# SSFocuser-B-TMC2208-KCTW.net
KiCad netlist of a schematic drawn in Altium Designer
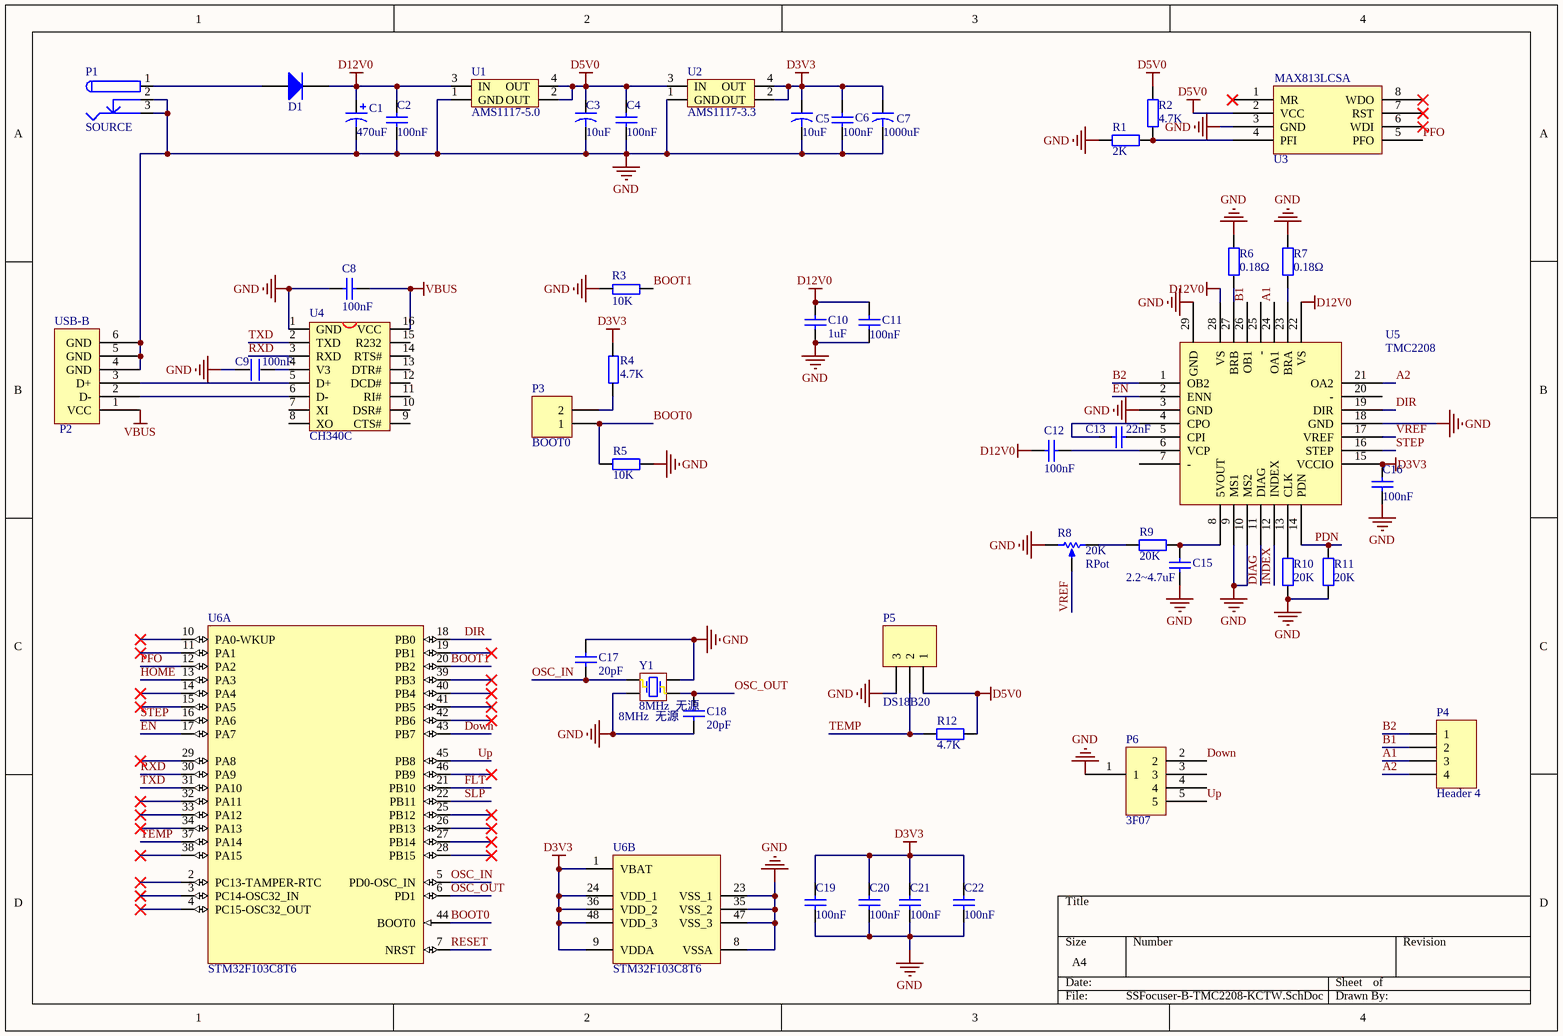
[diagram p0: SSFocuser-B-TMC2208-KCTW.SchDoc]

(export (version "E")
  (design (tool "Eeschema 10.0.6"))
  (components
    (comp (ref "C1")
      (value "470uF")
      (footprint "16V/470U(CD10X10D5)")
      (description "470UF      16V      CD10X10D5")
      (libsource (lib "平台原理图symbol图库V1.0") (part "C470UF016S"))
    )
    (comp (ref "C2")
      (value "100nF")
      (footprint "0603C")
      (description "Capacitor")
      (fields (field (name "PUBLISHER") "Altium Limited"))
      (libsource (lib "Crazy_PCB") (part "Cap"))
    )
    (comp (ref "C3")
      (value "10uF")
      (footprint "3216")
      (fields (field (name "VAULE") "10uF"))
      (libsource (lib "Crazy_PCB") (part "CAP2"))
    )
    (comp (ref "C4")
      (value "100nF")
      (footprint "0603C")
      (description "Capacitor")
      (fields (field (name "PUBLISHER") "Altium Limited"))
      (libsource (lib "Crazy_PCB") (part "Cap"))
    )
    (comp (ref "C5")
      (value "10uF")
      (footprint "3216")
      (fields (field (name "VAULE") "10uF"))
      (libsource (lib "Crazy_PCB") (part "CAP2"))
    )
    (comp (ref "C6")
      (value "100nF")
      (footprint "0603C")
      (description "Capacitor")
      (fields (field (name "PUBLISHER") "Altium Limited"))
      (libsource (lib "Crazy_PCB") (part "Cap"))
    )
    (comp (ref "C7")
      (value "1000uF")
      (footprint "16V/470U(CD10X10D5)")
      (fields (field (name "VAULE") "1000uF"))
      (libsource (lib "Crazy_PCB") (part "CAP2"))
    )
    (comp (ref "C8")
      (value "100nF")
      (footprint "0603C")
      (description "Capacitor")
      (fields (field (name "PUBLISHER") "Altium Limited"))
      (libsource (lib "Crazy_PCB") (part "Cap"))
    )
    (comp (ref "C9")
      (value "100nF")
      (footprint "0603C")
      (libsource (lib "WarShip V3 STM32103封装库") (part "C"))
    )
    (comp (ref "C10")
      (value "1uF")
      (footprint "1206C")
      (description "Capacitor")
      (fields (field (name "PUBLISHER") "Altium Limited"))
      (libsource (lib "Crazy_PCB") (part "Cap"))
    )
    (comp (ref "C11")
      (value "100nF")
      (footprint "0603C")
      (description "Capacitor")
      (fields (field (name "PUBLISHER") "Altium Limited"))
      (libsource (lib "Crazy_PCB") (part "Cap"))
    )
    (comp (ref "C12")
      (value "100nF")
      (footprint "0603C")
      (description "Capacitor")
      (fields (field (name "PUBLISHER") "Altium Limited"))
      (libsource (lib "Crazy_PCB") (part "Cap"))
    )
    (comp (ref "C13")
      (value "22nF")
      (footprint "0603C")
      (description "Capacitor")
      (fields (field (name "PUBLISHER") "Altium Limited"))
      (libsource (lib "Crazy_PCB") (part "Cap"))
    )
    (comp (ref "C15")
      (value "2.2~4.7uF")
      (footprint "0603C")
      (description "Capacitor")
      (fields (field (name "PUBLISHER") "Altium Limited"))
      (libsource (lib "Crazy_PCB") (part "Cap"))
    )
    (comp (ref "C16")
      (value "100nF")
      (footprint "0603C")
      (description "Capacitor")
      (fields (field (name "PUBLISHER") "Altium Limited"))
      (libsource (lib "Crazy_PCB") (part "Cap"))
    )
    (comp (ref "C17")
      (value "20pF")
      (footprint "0603C")
      (description "Capacitor")
      (fields (field (name "PUBLISHER") "Altium Limited"))
      (libsource (lib "JL_SCH") (part "Cap"))
    )
    (comp (ref "C18")
      (value "20pF")
      (footprint "0603C")
      (description "Capacitor")
      (fields (field (name "PUBLISHER") "Altium Limited"))
      (libsource (lib "JL_SCH") (part "Cap"))
    )
    (comp (ref "C19")
      (value "100nF")
      (footprint "0603C")
      (description "Capacitor")
      (fields (field (name "PUBLISHER") "Altium Limited"))
      (libsource (lib "Crazy_PCB") (part "Cap"))
    )
    (comp (ref "C20")
      (value "100nF")
      (footprint "0603C")
      (description "Capacitor")
      (fields (field (name "PUBLISHER") "Altium Limited"))
      (libsource (lib "Crazy_PCB") (part "Cap"))
    )
    (comp (ref "C21")
      (value "100nF")
      (footprint "0603C")
      (description "Capacitor")
      (fields (field (name "PUBLISHER") "Altium Limited"))
      (libsource (lib "Crazy_PCB") (part "Cap"))
    )
    (comp (ref "C22")
      (value "100nF")
      (footprint "0603C")
      (description "Capacitor")
      (fields (field (name "PUBLISHER") "Altium Limited"))
      (libsource (lib "Crazy_PCB") (part "Cap"))
    )
    (comp (ref "D1")
      (value "M7")
      (footprint "DO-214AC")
      (description "High Conductance Fast Diode")
      (fields (field (name "PUBLISHER") "Altium Limited"))
      (libsource (lib "Crazy_PCB") (part "Diode"))
    )
    (comp (ref "P1")
      (value "SOURCE")
      (footprint "DC005")
      (fields (field (name "PUBLISHER") "Altium Limited"))
      (libsource (lib "Crazy_PCB") (part "SOURCE"))
    )
    (comp (ref "P2") (value "USB-B") (footprint "USB-B") (libsource (lib "DX") (part "USB-B")))
    (comp (ref "P3")
      (value "BOOT0")
      (footprint "HDR1X2")
      (description "Header, 2-Pin")
      (fields (field (name "PUBLISHER") "Altium Limited"))
      (libsource (lib "Miscellaneous Connectors") (part "MHDR1X2"))
    )
    (comp (ref "P4")
      (value "Header 4")
      (footprint "XH_4_V")
      (description "Header, 4-Pin")
      (fields (field (name "PUBLISHER") "Altium Limited"))
      (libsource (lib "Miscellaneous Connectors") (part "Header 4"))
    )
    (comp (ref "P5")
      (value "DS18B20")
      (footprint "TO-92B")
      (description "Header, 3-Pin")
      (fields (field (name "PUBLISHER") "Altium Limited"))
      (libsource (lib "Miscellaneous Connectors") (part "Header 3"))
    )
    (comp (ref "P6")
      (value "3F07")
      (footprint "3F07")
      (description "EarPhone3.5")
      (libsource (lib "SS") (part "3F07"))
    )
    (comp (ref "R1")
      (value "2K")
      (footprint "0603R")
      (description "Resistor")
      (fields (field (name "PUBLISHER") "Altium Limited"))
      (libsource (lib "") (part "RES_3"))
    )
    (comp (ref "R2")
      (value "4.7K")
      (footprint "0603R")
      (description "Resistor")
      (fields (field (name "PUBLISHER") "Altium Limited"))
      (libsource (lib "Crazy_PCB") (part "RES"))
    )
    (comp (ref "R3") (value "10K") (footprint "0603R") (libsource (lib "WarShip V3 STM32103封装库") (part "R")))
    (comp (ref "R4") (value "4.7K") (footprint "0603R") (libsource (lib "WarShip V3 STM32103封装库") (part "R")))
    (comp (ref "R5")
      (value "10K")
      (footprint "0603R")
      (description "Resistor")
      (fields (field (name "PUBLISHER") "Altium Limited"))
      (libsource (lib "") (part "RES_2"))
    )
    (comp (ref "R6")
      (value "0.18Ω")
      (footprint "1206R")
      (description "Resistor")
      (fields (field (name "PUBLISHER") "Altium Limited"))
      (libsource (lib "") (part "RES_1"))
    )
    (comp (ref "R7")
      (value "0.18Ω")
      (footprint "1206R")
      (description "Resistor")
      (fields (field (name "PUBLISHER") "Altium Limited"))
      (libsource (lib "") (part "RES_1"))
    )
    (comp (ref "R8")
      (value "RPot")
      (footprint "VR_SMD")
      (description "Potentiometer")
      (fields (field (name "ALTIUM_VALUE") "20K") (field (name "PUBLISHER") "Altium Limited"))
      (libsource (lib "Miscellaneous Devices") (part "RPot"))
    )
    (comp (ref "R9")
      (value "20K")
      (footprint "0603R")
      (description "Resistor")
      (fields (field (name "PUBLISHER") "Altium Limited"))
      (libsource (lib "") (part "RES_3"))
    )
    (comp (ref "R10")
      (value "20K")
      (footprint "0603R")
      (description "Resistor")
      (fields (field (name "PUBLISHER") "Altium Limited"))
      (libsource (lib "Crazy_PCB") (part "RES"))
    )
    (comp (ref "R11")
      (value "20K")
      (footprint "0603R")
      (description "Resistor")
      (fields (field (name "PUBLISHER") "Altium Limited"))
      (libsource (lib "Crazy_PCB") (part "RES"))
    )
    (comp (ref "R12")
      (value "4.7K")
      (footprint "0603R")
      (description "Resistor")
      (fields (field (name "PUBLISHER") "Altium Limited"))
      (libsource (lib "") (part "RES_2"))
    )
    (comp (ref "U1")
      (value "AMS1117-5.0")
      (footprint "SOT223")
      (libsource (lib "MiniSTM32 V3.0封装库") (part "AMS1117"))
    )
    (comp (ref "U2")
      (value "AMS1117-3.3")
      (footprint "SOT223")
      (libsource (lib "MiniSTM32 V3.0封装库") (part "AMS1117"))
    )
    (comp (ref "U3") (value "MAX813LCSA") (footprint "SOP-8") (libsource (lib "DX") (part "MAX813L")))
    (comp (ref "U4")
      (value "CH340C")
      (footprint "SO-16")
      (description "USB2UART")
      (libsource (lib "WarShip V3 STM32103封装库") (part "CH340G"))
    )
    (comp (ref "U5") (value "TMC2208") (footprint "QFN28") (libsource (lib "SS") (part "TMC2208")))
    (comp (ref "U6")
      (value "STM32F103C8T6")
      (footprint "LQFP48_N")
      (libsource (lib "STMicroelectronics STM32 F1") (part "STM32F103C8T6"))
    )
    (comp (ref "Y1")
      (value "8MHz  无源")
      (footprint "X3225")
      (description "Crystal Oscillator")
      (fields (field (name "ALTIUM_VALUE") "8MHz  无源") (field (name "PUBLISHER") "Altium Limited"))
      (libsource (lib "JL_SCH") (part "XTAL_1"))
    )
  )
  (nets
    (net (code "1") (name "/A1") (class "Default")
      (node (ref "P4") (pin "3") (pinfunction "3_3") (pintype "passive"))
      (node (ref "U5") (pin "24") (pinfunction "OA1_24") (pintype "passive"))
    )
    (net (code "2") (name "/A2") (class "Default")
      (node (ref "P4") (pin "4") (pinfunction "4_4") (pintype "passive"))
      (node (ref "U5") (pin "21") (pinfunction "OA2_21") (pintype "passive"))
    )
    (net (code "3") (name "/B1") (class "Default")
      (node (ref "P4") (pin "2") (pinfunction "2_2") (pintype "passive"))
      (node (ref "U5") (pin "26") (pinfunction "OB1_26") (pintype "passive"))
    )
    (net (code "4") (name "/B2") (class "Default")
      (node (ref "P4") (pin "1") (pinfunction "1_1") (pintype "passive"))
      (node (ref "U5") (pin "1") (pinfunction "OB2_1") (pintype "passive"))
    )
    (net (code "5") (name "/BOOT0") (class "Default")
      (node (ref "P3") (pin "1") (pinfunction "1_1") (pintype "passive"))
      (node (ref "R5") (pin "1") (pinfunction "1_1") (pintype "passive"))
      (node (ref "U6") (pin "44") (pinfunction "BOOT0_44") (pintype "input"))
    )
    (net (code "6") (name "/BOOT1") (class "Default")
      (node (ref "R3") (pin "2") (pintype "passive"))
      (node (ref "U6") (pin "20") (pinfunction "PB2_20") (pintype "bidirectional"))
    )
    (net (code "7") (name "/DIAG") (class "Default")
      (node (ref "U5") (pin "11") (pinfunction "DIAG_11") (pintype "passive"))
    )
    (net (code "8") (name "/DIR") (class "Default")
      (node (ref "U5") (pin "19") (pinfunction "DIR_19") (pintype "passive"))
      (node (ref "U6") (pin "18") (pinfunction "PB0_18") (pintype "bidirectional"))
    )
    (net (code "9") (name "/Down") (class "Default")
      (node (ref "P6") (pin "2") (pinfunction "2_2") (pintype "passive"))
      (node (ref "U6") (pin "43") (pinfunction "PB7_43") (pintype "bidirectional"))
    )
    (net (code "10") (name "/EN") (class "Default")
      (node (ref "U5") (pin "2") (pinfunction "ENN_2") (pintype "passive"))
      (node (ref "U6") (pin "17") (pinfunction "PA7_17") (pintype "bidirectional"))
    )
    (net (code "11") (name "/FLT") (class "Default")
      (node (ref "U6") (pin "21") (pinfunction "PB10_21") (pintype "bidirectional"))
    )
    (net (code "12") (name "/HOME") (class "Default")
      (node (ref "U6") (pin "13") (pinfunction "PA3_13") (pintype "bidirectional"))
    )
    (net (code "13") (name "/INDEX") (class "Default")
      (node (ref "U5") (pin "12") (pinfunction "INDEX_12") (pintype "passive"))
    )
    (net (code "14") (name "/OSC_IN") (class "Default")
      (node (ref "C17") (pin "1") (pinfunction "1_1") (pintype "passive"))
      (node (ref "U6") (pin "5") (pinfunction "PD0-OSC_IN_5") (pintype "bidirectional"))
      (node (ref "Y1") (pin "1") (pinfunction "OSC1_1") (pintype "passive"))
    )
    (net (code "15") (name "/OSC_OUT") (class "Default")
      (node (ref "C18") (pin "1") (pinfunction "1_1") (pintype "passive"))
      (node (ref "U6") (pin "6") (pinfunction "PD1_6") (pintype "bidirectional"))
      (node (ref "Y1") (pin "3") (pinfunction "OSC2_3") (pintype "passive"))
    )
    (net (code "16") (name "/PDN") (class "Default")
      (node (ref "R11") (pin "2") (pinfunction "2_2") (pintype "passive"))
      (node (ref "U5") (pin "14") (pinfunction "PDN_14") (pintype "passive"))
    )
    (net (code "17") (name "/PFO") (class "Default")
      (node (ref "U3") (pin "5") (pinfunction "PFO_5") (pintype "passive"))
      (node (ref "U6") (pin "12") (pinfunction "PA2_12") (pintype "bidirectional"))
    )
    (net (code "18") (name "/RESET") (class "Default")
      (node (ref "U6") (pin "7") (pinfunction "NRST_7") (pintype "bidirectional"))
    )
    (net (code "19") (name "/RXD") (class "Default")
      (node (ref "U4") (pin "3") (pinfunction "RXD_3") (pintype "passive"))
      (node (ref "U6") (pin "30") (pinfunction "PA9_30") (pintype "bidirectional"))
    )
    (net (code "20") (name "/SLP") (class "Default")
      (node (ref "U6") (pin "22") (pinfunction "PB11_22") (pintype "bidirectional"))
    )
    (net (code "21") (name "/STEP") (class "Default")
      (node (ref "U5") (pin "16") (pinfunction "STEP_16") (pintype "passive"))
      (node (ref "U6") (pin "16") (pinfunction "PA6_16") (pintype "bidirectional"))
    )
    (net (code "22") (name "/TEMP") (class "Default")
      (node (ref "P5") (pin "2") (pinfunction "2_2") (pintype "passive"))
      (node (ref "R12") (pin "1") (pinfunction "1_1") (pintype "passive"))
      (node (ref "U6") (pin "37") (pinfunction "PA14_37") (pintype "bidirectional"))
    )
    (net (code "23") (name "/TXD") (class "Default")
      (node (ref "U4") (pin "2") (pinfunction "TXD_2") (pintype "passive"))
      (node (ref "U6") (pin "31") (pinfunction "PA10_31") (pintype "bidirectional"))
    )
    (net (code "24") (name "/Up") (class "Default")
      (node (ref "P6") (pin "5") (pinfunction "5_5") (pintype "passive"))
      (node (ref "U6") (pin "45") (pinfunction "PB8_45") (pintype "bidirectional"))
    )
    (net (code "25") (name "/VREF") (class "Default")
      (node (ref "R8") (pin "3") (pinfunction "TAP_3") (pintype "passive"))
      (node (ref "U5") (pin "17") (pinfunction "VREF_17") (pintype "passive"))
    )
    (net (code "26") (name "D3V3") (class "Default")
      (node (ref "C16") (pin "2") (pinfunction "2_2") (pintype "passive"))
      (node (ref "C19") (pin "2") (pinfunction "2_2") (pintype "passive"))
      (node (ref "C20") (pin "2") (pinfunction "2_2") (pintype "passive"))
      (node (ref "C21") (pin "2") (pinfunction "2_2") (pintype "passive"))
      (node (ref "C22") (pin "2") (pinfunction "2_2") (pintype "passive"))
      (node (ref "C5") (pin "1") (pinfunction "1_1") (pintype "passive"))
      (node (ref "C6") (pin "2") (pinfunction "2_2") (pintype "passive"))
      (node (ref "C7") (pin "1") (pinfunction "1_1") (pintype "passive"))
      (node (ref "R4") (pin "2") (pintype "passive"))
      (node (ref "U2") (pin "2") (pinfunction "OUT_2") (pintype "passive"))
      (node (ref "U2") (pin "4") (pinfunction "OUT_4") (pintype "passive"))
      (node (ref "U5") (pin "15") (pinfunction "VCCIO_15") (pintype "passive"))
      (node (ref "U6") (pin "1") (pinfunction "VBAT_1") (pintype "power_in"))
      (node (ref "U6") (pin "24") (pinfunction "VDD_1_24") (pintype "power_in"))
      (node (ref "U6") (pin "36") (pinfunction "VDD_2_36") (pintype "power_in"))
      (node (ref "U6") (pin "48") (pinfunction "VDD_3_48") (pintype "power_in"))
      (node (ref "U6") (pin "9") (pinfunction "VDDA_9") (pintype "power_in"))
    )
    (net (code "27") (name "D5V0") (class "Default")
      (node (ref "C3") (pin "1") (pinfunction "1_1") (pintype "passive"))
      (node (ref "C4") (pin "2") (pinfunction "2_2") (pintype "passive"))
      (node (ref "P5") (pin "1") (pinfunction "1_1") (pintype "passive"))
      (node (ref "R12") (pin "2") (pinfunction "2_2") (pintype "passive"))
      (node (ref "R2") (pin "2") (pinfunction "2_2") (pintype "passive"))
      (node (ref "U1") (pin "2") (pinfunction "OUT_2") (pintype "passive"))
      (node (ref "U1") (pin "4") (pinfunction "OUT_4") (pintype "passive"))
      (node (ref "U2") (pin "3") (pinfunction "IN_3") (pintype "passive"))
      (node (ref "U3") (pin "2") (pinfunction "VCC_2") (pintype "passive"))
    )
    (net (code "28") (name "D12V0") (class "Default")
      (node (ref "C1") (pin "1") (pinfunction "1_1") (pintype "passive"))
      (node (ref "C10") (pin "1") (pinfunction "1_1") (pintype "passive"))
      (node (ref "C11") (pin "2") (pinfunction "2_2") (pintype "passive"))
      (node (ref "C12") (pin "2") (pinfunction "2_2") (pintype "passive"))
      (node (ref "C2") (pin "2") (pinfunction "2_2") (pintype "passive"))
      (node (ref "D1") (pin "2") (pinfunction "K_2") (pintype "passive"))
      (node (ref "U1") (pin "3") (pinfunction "IN_3") (pintype "passive"))
      (node (ref "U5") (pin "22") (pinfunction "VS_22") (pintype "passive"))
      (node (ref "U5") (pin "28") (pinfunction "VS_28") (pintype "passive"))
    )
    (net (code "29") (name "GND") (class "Default")
      (node (ref "C1") (pin "2") (pinfunction "2_2") (pintype "passive"))
      (node (ref "C10") (pin "2") (pinfunction "2_2") (pintype "passive"))
      (node (ref "C11") (pin "1") (pinfunction "1_1") (pintype "passive"))
      (node (ref "C15") (pin "1") (pinfunction "1_1") (pintype "passive"))
      (node (ref "C16") (pin "1") (pinfunction "1_1") (pintype "passive"))
      (node (ref "C17") (pin "2") (pinfunction "2_2") (pintype "passive"))
      (node (ref "C18") (pin "2") (pinfunction "2_2") (pintype "passive"))
      (node (ref "C19") (pin "1") (pinfunction "1_1") (pintype "passive"))
      (node (ref "C2") (pin "1") (pinfunction "1_1") (pintype "passive"))
      (node (ref "C20") (pin "1") (pinfunction "1_1") (pintype "passive"))
      (node (ref "C21") (pin "1") (pinfunction "1_1") (pintype "passive"))
      (node (ref "C22") (pin "1") (pinfunction "1_1") (pintype "passive"))
      (node (ref "C3") (pin "2") (pinfunction "2_2") (pintype "passive"))
      (node (ref "C4") (pin "1") (pinfunction "1_1") (pintype "passive"))
      (node (ref "C5") (pin "2") (pinfunction "2_2") (pintype "passive"))
      (node (ref "C6") (pin "1") (pinfunction "1_1") (pintype "passive"))
      (node (ref "C7") (pin "2") (pinfunction "2_2") (pintype "passive"))
      (node (ref "C8") (pin "1") (pinfunction "1_1") (pintype "passive"))
      (node (ref "C9") (pin "1") (pintype "passive"))
      (node (ref "P1") (pin "2") (pinfunction "2_2") (pintype "power_in"))
      (node (ref "P1") (pin "3") (pinfunction "3_3") (pintype "power_in"))
      (node (ref "P2") (pin "4") (pinfunction "GND_4") (pintype "passive"))
      (node (ref "P2") (pin "5") (pinfunction "GND_5") (pintype "passive"))
      (node (ref "P2") (pin "6") (pinfunction "GND_6") (pintype "passive"))
      (node (ref "P5") (pin "3") (pinfunction "3_3") (pintype "passive"))
      (node (ref "P6") (pin "1") (pinfunction "1_1") (pintype "passive"))
      (node (ref "R1") (pin "2") (pinfunction "2_2") (pintype "passive"))
      (node (ref "R10") (pin "1") (pinfunction "1_1") (pintype "passive"))
      (node (ref "R11") (pin "1") (pinfunction "1_1") (pintype "passive"))
      (node (ref "R3") (pin "1") (pintype "passive"))
      (node (ref "R5") (pin "2") (pinfunction "2_2") (pintype "passive"))
      (node (ref "R6") (pin "1") (pinfunction "1_1") (pintype "passive"))
      (node (ref "R7") (pin "1") (pinfunction "1_1") (pintype "passive"))
      (node (ref "R8") (pin "1") (pinfunction "TOP_1") (pintype "passive"))
      (node (ref "U1") (pin "1") (pinfunction "GND_1") (pintype "passive"))
      (node (ref "U2") (pin "1") (pinfunction "GND_1") (pintype "passive"))
      (node (ref "U3") (pin "3") (pinfunction "GND_3") (pintype "passive"))
      (node (ref "U4") (pin "1") (pinfunction "GND_1") (pintype "passive"))
      (node (ref "U5") (pin "10") (pinfunction "MS2_10") (pintype "passive"))
      (node (ref "U5") (pin "18") (pinfunction "GND_18") (pintype "passive"))
      (node (ref "U5") (pin "29") (pinfunction "GND_29") (pintype "passive"))
      (node (ref "U5") (pin "3") (pinfunction "GND_3") (pintype "passive"))
      (node (ref "U5") (pin "9") (pinfunction "MS1_9") (pintype "passive"))
      (node (ref "U6") (pin "23") (pinfunction "VSS_1_23") (pintype "power_in"))
      (node (ref "U6") (pin "35") (pinfunction "VSS_2_35") (pintype "power_in"))
      (node (ref "U6") (pin "47") (pinfunction "VSS_3_47") (pintype "power_in"))
      (node (ref "U6") (pin "8") (pinfunction "VSSA_8") (pintype "power_in"))
      (node (ref "Y1") (pin "2") (pinfunction "NA_2") (pintype "passive"))
      (node (ref "Y1") (pin "4") (pinfunction "NA_4") (pintype "passive"))
    )
    (net (code "30") (name "Net-(D1-A)") (class "Default")
      (node (ref "D1") (pin "1") (pinfunction "A_1") (pintype "passive"))
      (node (ref "P1") (pin "1") (pinfunction "1_1") (pintype "power_in"))
    )
    (net (code "31") (name "Net-(P2-D+)") (class "Default")
      (node (ref "P2") (pin "3") (pinfunction "D+_3") (pintype "passive"))
      (node (ref "U4") (pin "5") (pinfunction "D+_5") (pintype "passive"))
    )
    (net (code "32") (name "Net-(P2-D-)") (class "Default")
      (node (ref "P2") (pin "2") (pinfunction "D-_2") (pintype "passive"))
      (node (ref "U4") (pin "6") (pinfunction "D-_6") (pintype "passive"))
    )
    (net (code "33") (name "Net-(P3-Pad2)") (class "Default")
      (node (ref "P3") (pin "2") (pinfunction "2_2") (pintype "passive"))
      (node (ref "R4") (pin "1") (pintype "passive"))
    )
    (net (code "34") (name "Net-(R8-BOT)") (class "Default")
      (node (ref "R8") (pin "2") (pinfunction "BOT_2") (pintype "passive"))
      (node (ref "R9") (pin "2") (pinfunction "2_2") (pintype "passive"))
    )
    (net (code "35") (name "Net-(U3-PFI)") (class "Default")
      (node (ref "R1") (pin "1") (pinfunction "1_1") (pintype "passive"))
      (node (ref "R2") (pin "1") (pinfunction "1_1") (pintype "passive"))
      (node (ref "U3") (pin "4") (pinfunction "PFI_4") (pintype "passive"))
    )
    (net (code "36") (name "Net-(U4-V3)") (class "Default")
      (node (ref "C9") (pin "2") (pintype "passive"))
      (node (ref "U4") (pin "4") (pinfunction "V3_4") (pintype "passive"))
    )
    (net (code "37") (name "Net-(U5-5VOUT)") (class "Default")
      (node (ref "C15") (pin "2") (pinfunction "2_2") (pintype "passive"))
      (node (ref "R9") (pin "1") (pinfunction "1_1") (pintype "passive"))
      (node (ref "U5") (pin "8") (pinfunction "5VOUT_8") (pintype "passive"))
    )
    (net (code "38") (name "Net-(U5-BRA)") (class "Default")
      (node (ref "R7") (pin "2") (pinfunction "2_2") (pintype "passive"))
      (node (ref "U5") (pin "23") (pinfunction "BRA_23") (pintype "passive"))
    )
    (net (code "39") (name "Net-(U5-BRB)") (class "Default")
      (node (ref "R6") (pin "2") (pinfunction "2_2") (pintype "passive"))
      (node (ref "U5") (pin "27") (pinfunction "BRB_27") (pintype "passive"))
    )
    (net (code "40") (name "Net-(U5-CLK)") (class "Default")
      (node (ref "R10") (pin "2") (pinfunction "2_2") (pintype "passive"))
      (node (ref "U5") (pin "13") (pinfunction "CLK_13") (pintype "passive"))
    )
    (net (code "41") (name "Net-(U5-CPI)") (class "Default")
      (node (ref "C13") (pin "1") (pinfunction "1_1") (pintype "passive"))
      (node (ref "U5") (pin "5") (pinfunction "CPI_5") (pintype "passive"))
    )
    (net (code "42") (name "Net-(U5-CPO)") (class "Default")
      (node (ref "C13") (pin "2") (pinfunction "2_2") (pintype "passive"))
      (node (ref "U5") (pin "4") (pinfunction "CPO_4") (pintype "passive"))
    )
    (net (code "43") (name "Net-(U5-VCP)") (class "Default")
      (node (ref "C12") (pin "1") (pinfunction "1_1") (pintype "passive"))
      (node (ref "U5") (pin "6") (pinfunction "VCP_6") (pintype "passive"))
    )
    (net (code "44") (name "VBUS") (class "Default")
      (node (ref "C8") (pin "2") (pinfunction "2_2") (pintype "passive"))
      (node (ref "P2") (pin "1") (pinfunction "VCC_1") (pintype "passive"))
      (node (ref "U4") (pin "16") (pinfunction "VCC_16") (pintype "passive"))
    )
    (net (code "45") (name "unconnected-(P6-Pad3)") (class "Default")
      (node (ref "P6") (pin "3") (pinfunction "3_3") (pintype "passive"))
    )
    (net (code "46") (name "unconnected-(P6-Pad4)") (class "Default")
      (node (ref "P6") (pin "4") (pinfunction "4_4") (pintype "passive"))
    )
    (net (code "47") (name "unconnected-(U3-MR-Pad1)") (class "Default")
      (node (ref "U3") (pin "1") (pinfunction "MR_1") (pintype "passive+no_connect"))
    )
    (net (code "48") (name "unconnected-(U3-RST-Pad7)") (class "Default")
      (node (ref "U3") (pin "7") (pinfunction "RST_7") (pintype "passive+no_connect"))
    )
    (net (code "49") (name "unconnected-(U3-WDI-Pad6)") (class "Default")
      (node (ref "U3") (pin "6") (pinfunction "WDI_6") (pintype "passive+no_connect"))
    )
    (net (code "50") (name "unconnected-(U3-WDO-Pad8)") (class "Default")
      (node (ref "U3") (pin "8") (pinfunction "WDO_8") (pintype "passive+no_connect"))
    )
    (net (code "51") (name "unconnected-(U4-CTS#-Pad9)") (class "Default")
      (node (ref "U4") (pin "9") (pinfunction "CTS#_9") (pintype "passive"))
    )
    (net (code "52") (name "unconnected-(U4-DCD#-Pad12)") (class "Default")
      (node (ref "U4") (pin "12") (pinfunction "DCD#_12") (pintype "passive"))
    )
    (net (code "53") (name "unconnected-(U4-DSR#-Pad10)") (class "Default")
      (node (ref "U4") (pin "10") (pinfunction "DSR#_10") (pintype "passive"))
    )
    (net (code "54") (name "unconnected-(U4-DTR#-Pad13)") (class "Default")
      (node (ref "U4") (pin "13") (pinfunction "DTR#_13") (pintype "passive"))
    )
    (net (code "55") (name "unconnected-(U4-R232-Pad15)") (class "Default")
      (node (ref "U4") (pin "15") (pinfunction "R232_15") (pintype "passive"))
    )
    (net (code "56") (name "unconnected-(U4-RI#-Pad11)") (class "Default")
      (node (ref "U4") (pin "11") (pinfunction "RI#_11") (pintype "passive"))
    )
    (net (code "57") (name "unconnected-(U4-RTS#-Pad14)") (class "Default")
      (node (ref "U4") (pin "14") (pinfunction "RTS#_14") (pintype "passive"))
    )
    (net (code "58") (name "unconnected-(U4-XI-Pad7)") (class "Default")
      (node (ref "U4") (pin "7") (pinfunction "XI_7") (pintype "passive"))
    )
    (net (code "59") (name "unconnected-(U4-XO-Pad8)") (class "Default")
      (node (ref "U4") (pin "8") (pinfunction "XO_8") (pintype "passive"))
    )
    (net (code "60") (name "unconnected-(U5---Pad7)") (class "Default")
      (node (ref "U5") (pin "7") (pinfunction "-_7") (pintype "passive"))
    )
    (net (code "61") (name "unconnected-(U5---Pad20)") (class "Default")
      (node (ref "U5") (pin "20") (pinfunction "-_20") (pintype "passive"))
    )
    (net (code "62") (name "unconnected-(U5---Pad25)") (class "Default")
      (node (ref "U5") (pin "25") (pinfunction "-_25") (pintype "passive"))
    )
    (net (code "63") (name "unconnected-(U6A-PA0-WKUP-Pad10)") (class "Default")
      (node (ref "U6") (pin "10") (pinfunction "PA0-WKUP_10") (pintype "bidirectional+no_connect"))
    )
    (net (code "64") (name "unconnected-(U6A-PA1-Pad11)") (class "Default")
      (node (ref "U6") (pin "11") (pinfunction "PA1_11") (pintype "bidirectional+no_connect"))
    )
    (net (code "65") (name "unconnected-(U6A-PA4-Pad14)") (class "Default")
      (node (ref "U6") (pin "14") (pinfunction "PA4_14") (pintype "bidirectional+no_connect"))
    )
    (net (code "66") (name "unconnected-(U6A-PA5-Pad15)") (class "Default")
      (node (ref "U6") (pin "15") (pinfunction "PA5_15") (pintype "bidirectional+no_connect"))
    )
    (net (code "67") (name "unconnected-(U6A-PA8-Pad29)") (class "Default")
      (node (ref "U6") (pin "29") (pinfunction "PA8_29") (pintype "bidirectional+no_connect"))
    )
    (net (code "68") (name "unconnected-(U6A-PA11-Pad32)") (class "Default")
      (node (ref "U6") (pin "32") (pinfunction "PA11_32") (pintype "bidirectional+no_connect"))
    )
    (net (code "69") (name "unconnected-(U6A-PA12-Pad33)") (class "Default")
      (node (ref "U6") (pin "33") (pinfunction "PA12_33") (pintype "bidirectional+no_connect"))
    )
    (net (code "70") (name "unconnected-(U6A-PA13-Pad34)") (class "Default")
      (node (ref "U6") (pin "34") (pinfunction "PA13_34") (pintype "bidirectional+no_connect"))
    )
    (net (code "71") (name "unconnected-(U6A-PA15-Pad38)") (class "Default")
      (node (ref "U6") (pin "38") (pinfunction "PA15_38") (pintype "bidirectional+no_connect"))
    )
    (net (code "72") (name "unconnected-(U6A-PB1-Pad19)") (class "Default")
      (node (ref "U6") (pin "19") (pinfunction "PB1_19") (pintype "bidirectional+no_connect"))
    )
    (net (code "73") (name "unconnected-(U6A-PB3-Pad39)") (class "Default")
      (node (ref "U6") (pin "39") (pinfunction "PB3_39") (pintype "bidirectional+no_connect"))
    )
    (net (code "74") (name "unconnected-(U6A-PB4-Pad40)") (class "Default")
      (node (ref "U6") (pin "40") (pinfunction "PB4_40") (pintype "bidirectional+no_connect"))
    )
    (net (code "75") (name "unconnected-(U6A-PB5-Pad41)") (class "Default")
      (node (ref "U6") (pin "41") (pinfunction "PB5_41") (pintype "bidirectional+no_connect"))
    )
    (net (code "76") (name "unconnected-(U6A-PB6-Pad42)") (class "Default")
      (node (ref "U6") (pin "42") (pinfunction "PB6_42") (pintype "bidirectional+no_connect"))
    )
    (net (code "77") (name "unconnected-(U6A-PB9-Pad46)") (class "Default")
      (node (ref "U6") (pin "46") (pinfunction "PB9_46") (pintype "bidirectional+no_connect"))
    )
    (net (code "78") (name "unconnected-(U6A-PB12-Pad25)") (class "Default")
      (node (ref "U6") (pin "25") (pinfunction "PB12_25") (pintype "bidirectional+no_connect"))
    )
    (net (code "79") (name "unconnected-(U6A-PB13-Pad26)") (class "Default")
      (node (ref "U6") (pin "26") (pinfunction "PB13_26") (pintype "bidirectional+no_connect"))
    )
    (net (code "80") (name "unconnected-(U6A-PB14-Pad27)") (class "Default")
      (node (ref "U6") (pin "27") (pinfunction "PB14_27") (pintype "bidirectional+no_connect"))
    )
    (net (code "81") (name "unconnected-(U6A-PB15-Pad28)") (class "Default")
      (node (ref "U6") (pin "28") (pinfunction "PB15_28") (pintype "bidirectional+no_connect"))
    )
    (net (code "82") (name "unconnected-(U6A-PC13-TAMPER-RTC-Pad2)") (class "Default")
      (node (ref "U6") (pin "2") (pinfunction "PC13-TAMPER-RTC_2") (pintype "bidirectional+no_connect"))
    )
    (net (code "83") (name "unconnected-(U6A-PC14-OSC32_IN-Pad3)") (class "Default")
      (node (ref "U6") (pin "3") (pinfunction "PC14-OSC32_IN_3") (pintype "bidirectional+no_connect"))
    )
    (net (code "84") (name "unconnected-(U6A-PC15-OSC32_OUT-Pad4)") (class "Default")
      (node (ref "U6") (pin "4") (pinfunction "PC15-OSC32_OUT_4") (pintype "bidirectional+no_connect"))
    )
  )
)
